# Feedforward_Controller.net
KiCad netlist of a schematic drawn in Altium Designer
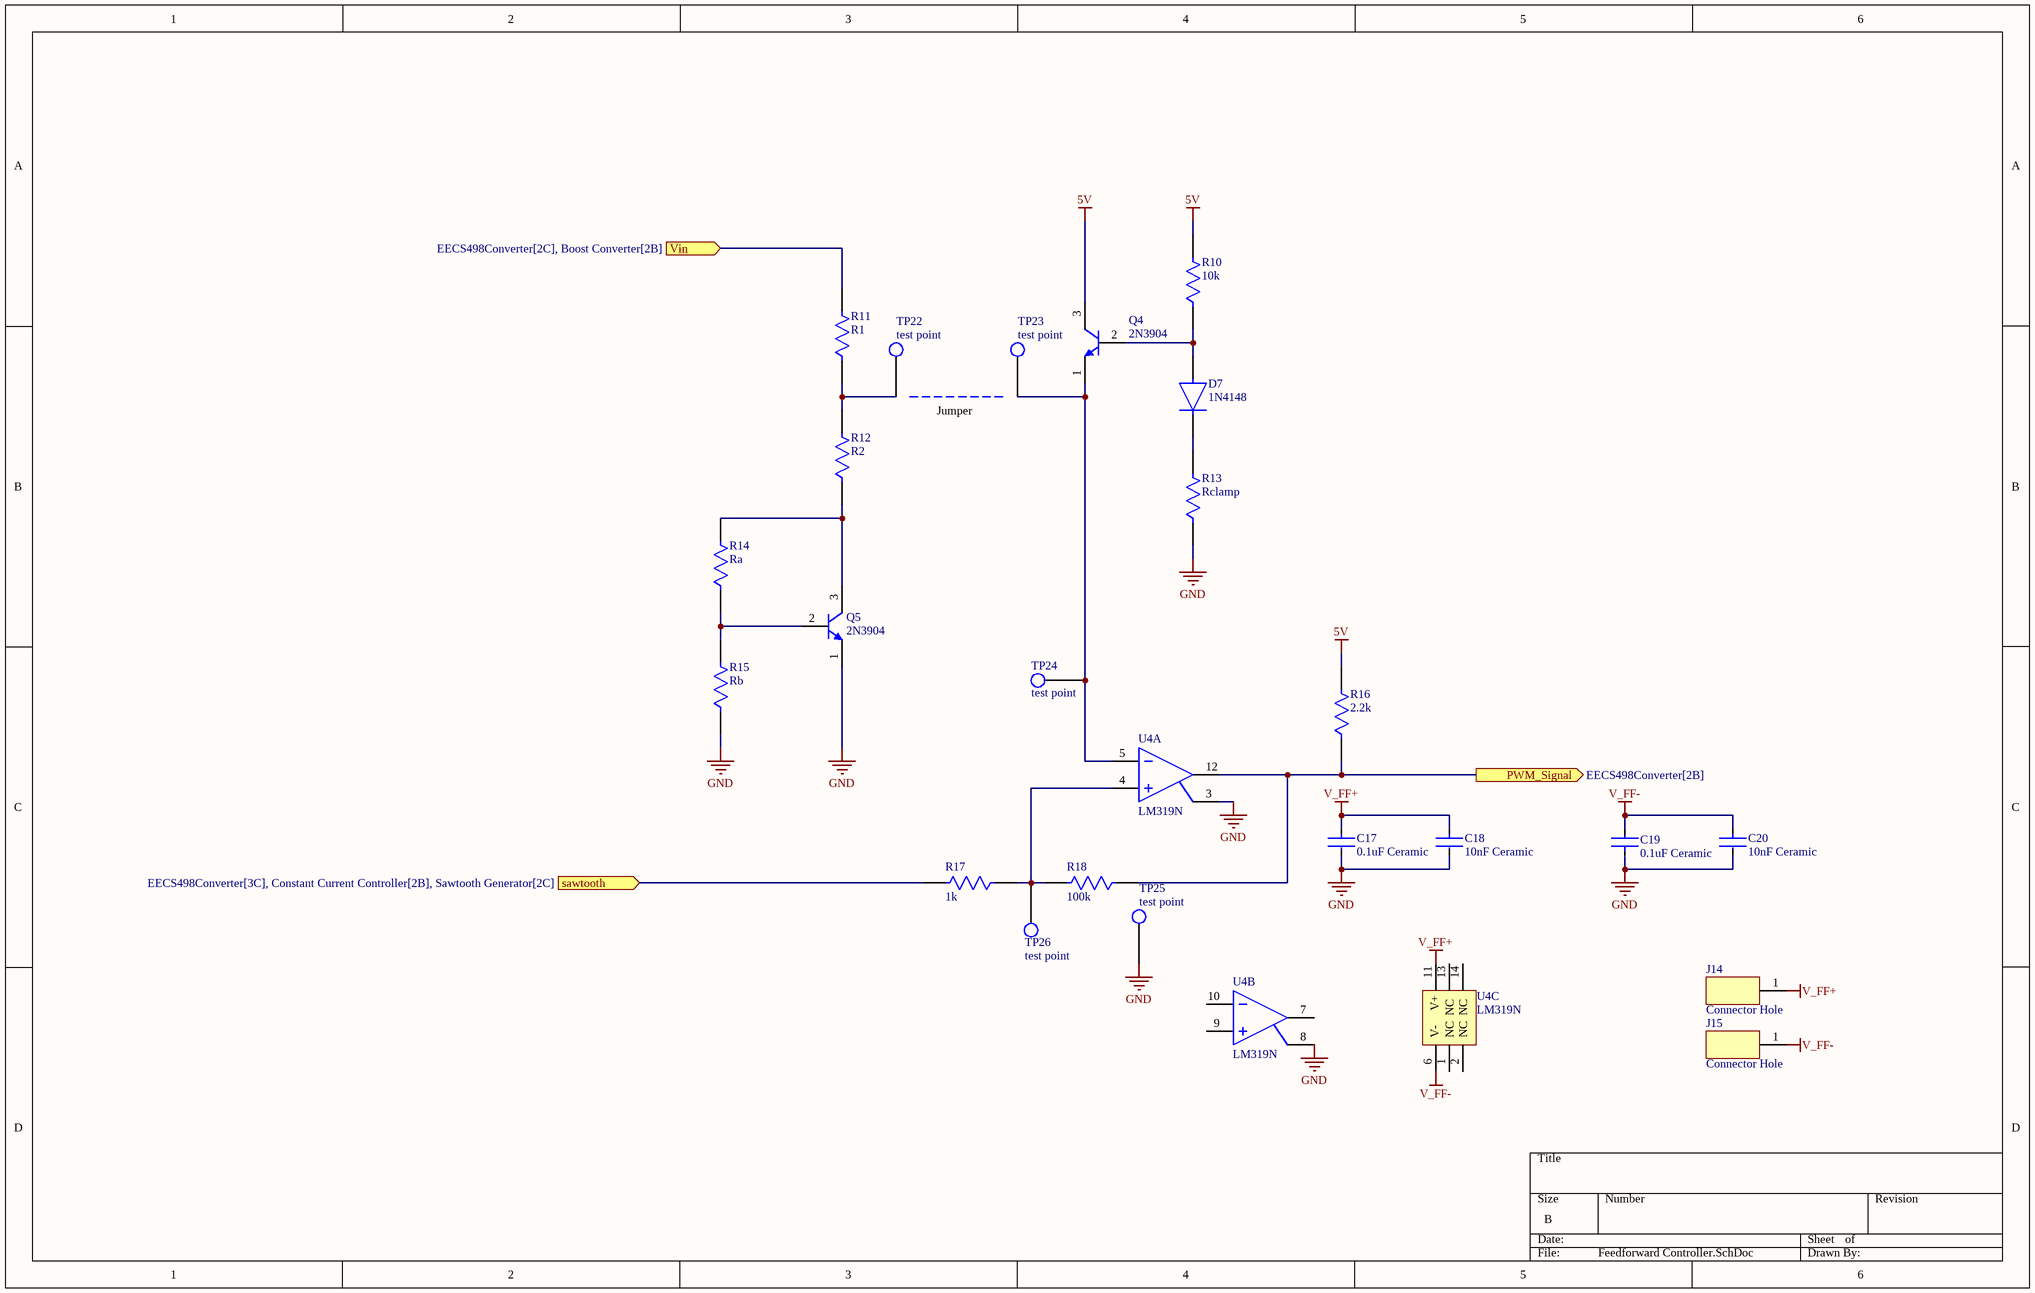
[diagram p0: Feedforward Controller.SchDoc]

(export (version "E")
  (design (tool "Eeschema 10.0.6"))
  (components
    (comp (ref "C17")
      (value "0.1uF Ceramic")
      (footprint "FP-K15H5-MFG")
      (description "CAP CER 0.1UF 50V X7R RADIAL")
      (fields (field (name "TOLERANCE") "10%") (field (name "VOLTAGE") "50V"))
      (libsource (lib "EECS498Converter") (part "0.1uF Capacitor"))
    )
    (comp (ref "C18")
      (value "10nF Ceramic")
      (footprint "FP-K15H5-MFG")
      (description "CAP CER 10nF 50V X7R RADIAL")
      (fields (field (name "TOLERANCE") "10%") (field (name "VOLTAGE") "50V"))
      (libsource (lib "EECS498Converter") (part "10nF Capacitor"))
    )
    (comp (ref "C19")
      (value "0.1uF Ceramic")
      (footprint "FP-K15H5-MFG")
      (description "CAP CER 0.1UF 50V X7R RADIAL")
      (fields (field (name "TOLERANCE") "10%") (field (name "VOLTAGE") "50V"))
      (libsource (lib "EECS498Converter") (part "0.1uF Capacitor"))
    )
    (comp (ref "C20")
      (value "10nF Ceramic")
      (footprint "FP-K15H5-MFG")
      (description "CAP CER 10nF 50V X7R RADIAL")
      (fields (field (name "TOLERANCE") "10%") (field (name "VOLTAGE") "50V"))
      (libsource (lib "EECS498Converter") (part "10nF Capacitor"))
    )
    (comp (ref "D7")
      (value "1N4148")
      (footprint "FP-1N4148-MFG")
      (description "DIODE GEN PURP 100V 200MA DO35")
      (fields (field (name "VOLTAGE") "100V"))
      (libsource (lib "EECS498Converter") (part "1N4148"))
    )
    (comp (ref "J14")
      (value "Connector Hole")
      (footprint "Connector Hole")
      (libsource (lib "EECS498Converter") (part "Connector Hole"))
    )
    (comp (ref "J15")
      (value "Connector Hole")
      (footprint "Connector Hole")
      (libsource (lib "EECS498Converter") (part "Connector Hole"))
    )
    (comp (ref "Q4")
      (value "2N3904")
      (footprint "2N3906TF")
      (description "General Purpose Transistor, NPN Silicon, 200 mA, 60 V, -55 to 150 degC, 3-Pin TO-92, RoHS, Bulk")
      (fields (field (name "MANUFACTURER") "ONSemiconductor"))
      (libsource (lib "EECS498Converter") (part "2N3904"))
    )
    (comp (ref "Q5")
      (value "2N3904")
      (footprint "2N3906TF")
      (description "General Purpose Transistor, NPN Silicon, 200 mA, 60 V, -55 to 150 degC, 3-Pin TO-92, RoHS, Bulk")
      (fields (field (name "MANUFACTURER") "ONSemiconductor"))
      (libsource (lib "EECS498Converter") (part "2N3904"))
    )
    (comp (ref "R10")
      (value "10k")
      (footprint "FP-RLR07-MFG")
      (description "Resistor, ± 1%, 250 mW, Axial Leaded, Metal Film, Military Reliability")
      (fields (field (name "TOLERANCE") "1%"))
      (libsource (lib "EECS498Converter") (part "Resistor"))
    )
    (comp (ref "R11")
      (value "R1")
      (footprint "FP-RLR07-MFG")
      (description "Resistor, ± 1%, 250 mW, Axial Leaded, Metal Film, Military Reliability")
      (fields (field (name "TOLERANCE") "1%"))
      (libsource (lib "EECS498Converter") (part "Resistor"))
    )
    (comp (ref "R12")
      (value "R2")
      (footprint "FP-RLR07-MFG")
      (description "Resistor, ± 1%, 250 mW, Axial Leaded, Metal Film, Military Reliability")
      (fields (field (name "TOLERANCE") "1%"))
      (libsource (lib "EECS498Converter") (part "Resistor"))
    )
    (comp (ref "R13")
      (value "Rclamp")
      (footprint "FP-RLR07-MFG")
      (description "Resistor, ± 1%, 250 mW, Axial Leaded, Metal Film, Military Reliability")
      (fields (field (name "TOLERANCE") "1%"))
      (libsource (lib "EECS498Converter") (part "Resistor"))
    )
    (comp (ref "R14")
      (value "Ra")
      (footprint "FP-RLR07-MFG")
      (description "Resistor, ± 1%, 250 mW, Axial Leaded, Metal Film, Military Reliability")
      (fields (field (name "TOLERANCE") "1%"))
      (libsource (lib "EECS498Converter") (part "Resistor"))
    )
    (comp (ref "R15")
      (value "Rb")
      (footprint "FP-RLR07-MFG")
      (description "Resistor, ± 1%, 250 mW, Axial Leaded, Metal Film, Military Reliability")
      (fields (field (name "TOLERANCE") "1%"))
      (libsource (lib "EECS498Converter") (part "Resistor"))
    )
    (comp (ref "R16")
      (value "2.2k")
      (footprint "FP-RLR07-MFG")
      (description "Resistor, ± 1%, 250 mW, Axial Leaded, Metal Film, Military Reliability")
      (fields (field (name "TOLERANCE") "1%"))
      (libsource (lib "EECS498Converter") (part "Resistor"))
    )
    (comp (ref "R17")
      (value "1k")
      (footprint "FP-RLR07-MFG")
      (description "Resistor, ± 1%, 250 mW, Axial Leaded, Metal Film, Military Reliability")
      (fields (field (name "TOLERANCE") "1%"))
      (libsource (lib "EECS498Converter") (part "Resistor"))
    )
    (comp (ref "R18")
      (value "100k")
      (footprint "FP-RLR07-MFG")
      (description "Resistor, ± 1%, 250 mW, Axial Leaded, Metal Film, Military Reliability")
      (fields (field (name "TOLERANCE") "1%"))
      (libsource (lib "EECS498Converter") (part "Resistor"))
    )
    (comp (ref "TP22")
      (value "test point")
      (footprint "test point")
      (libsource (lib "EECS498Converter") (part "test point"))
    )
    (comp (ref "TP23")
      (value "test point")
      (footprint "test point")
      (libsource (lib "EECS498Converter") (part "test point"))
    )
    (comp (ref "TP24")
      (value "test point")
      (footprint "test point")
      (libsource (lib "EECS498Converter") (part "test point"))
    )
    (comp (ref "TP25")
      (value "test point")
      (footprint "test point")
      (libsource (lib "EECS498Converter") (part "test point"))
    )
    (comp (ref "TP26")
      (value "test point")
      (footprint "test point")
      (libsource (lib "EECS498Converter") (part "test point"))
    )
    (comp (ref "U4")
      (value "LM319N")
      (footprint "LM319_DIP14")
      (description "High Speed Dual Comparator, 14-pin MDIP")
      (fields (field (name "MANUFACTURER") "Texas Instruments"))
      (libsource (lib "EECS498Converter") (part "LM319N"))
    )
  )
  (nets
    (net (code "1") (name "/PWM_Signal") (class "Default")
      (node (ref "R16") (pin "1") (pinfunction "1_1") (pintype "passive"))
      (node (ref "R18") (pin "1") (pinfunction "1_1") (pintype "passive"))
      (node (ref "U4") (pin "12") (pinfunction "OUT1_12") (pintype "passive"))
    )
    (net (code "2") (name "/Vin") (class "Default")
      (node (ref "R11") (pin "2") (pinfunction "2_2") (pintype "passive"))
    )
    (net (code "3") (name "/sawtooth") (class "Default")
      (node (ref "R17") (pin "2") (pinfunction "2_2") (pintype "passive"))
    )
    (net (code "4") (name "5V") (class "Default")
      (node (ref "Q4") (pin "3") (pinfunction "C_3") (pintype "passive"))
      (node (ref "R10") (pin "2") (pinfunction "2_2") (pintype "passive"))
      (node (ref "R16") (pin "2") (pinfunction "2_2") (pintype "passive"))
    )
    (net (code "5") (name "GND") (class "Default")
      (node (ref "C17") (pin "2") (pinfunction "2_2") (pintype "passive"))
      (node (ref "C18") (pin "2") (pinfunction "2_2") (pintype "passive"))
      (node (ref "C19") (pin "1") (pinfunction "1_1") (pintype "passive"))
      (node (ref "C20") (pin "2") (pinfunction "2_2") (pintype "passive"))
      (node (ref "Q5") (pin "1") (pinfunction "E_1") (pintype "passive"))
      (node (ref "R13") (pin "1") (pinfunction "1_1") (pintype "passive"))
      (node (ref "R15") (pin "1") (pinfunction "1_1") (pintype "passive"))
      (node (ref "TP25") (pin "1") (pintype "passive"))
      (node (ref "U4") (pin "3") (pinfunction "GND1_3") (pintype "passive"))
      (node (ref "U4") (pin "8") (pinfunction "GND2_8") (pintype "passive"))
    )
    (net (code "6") (name "Net-(D7-A)") (class "Default")
      (node (ref "D7") (pin "2") (pinfunction "A_2") (pintype "passive"))
      (node (ref "Q4") (pin "2") (pinfunction "B_2") (pintype "passive"))
      (node (ref "R10") (pin "1") (pinfunction "1_1") (pintype "passive"))
    )
    (net (code "7") (name "Net-(D7-C)") (class "Default")
      (node (ref "D7") (pin "1") (pinfunction "C_1") (pintype "passive"))
      (node (ref "R13") (pin "2") (pinfunction "2_2") (pintype "passive"))
    )
    (net (code "8") (name "Net-(Q4-E)") (class "Default")
      (node (ref "Q4") (pin "1") (pinfunction "E_1") (pintype "passive"))
      (node (ref "TP23") (pin "1") (pintype "passive"))
      (node (ref "TP24") (pin "1") (pintype "passive"))
      (node (ref "U4") (pin "5") (pinfunction "IN1-_5") (pintype "passive"))
    )
    (net (code "9") (name "Net-(Q5-B)") (class "Default")
      (node (ref "Q5") (pin "2") (pinfunction "B_2") (pintype "passive"))
      (node (ref "R14") (pin "1") (pinfunction "1_1") (pintype "passive"))
      (node (ref "R15") (pin "2") (pinfunction "2_2") (pintype "passive"))
    )
    (net (code "10") (name "Net-(Q5-C)") (class "Default")
      (node (ref "Q5") (pin "3") (pinfunction "C_3") (pintype "passive"))
      (node (ref "R12") (pin "1") (pinfunction "1_1") (pintype "passive"))
      (node (ref "R14") (pin "2") (pinfunction "2_2") (pintype "passive"))
    )
    (net (code "11") (name "Net-(R11-Pad1)") (class "Default")
      (node (ref "R11") (pin "1") (pinfunction "1_1") (pintype "passive"))
      (node (ref "R12") (pin "2") (pinfunction "2_2") (pintype "passive"))
      (node (ref "TP22") (pin "1") (pintype "passive"))
    )
    (net (code "12") (name "Net-(U4A-IN1+)") (class "Default")
      (node (ref "R17") (pin "1") (pinfunction "1_1") (pintype "passive"))
      (node (ref "R18") (pin "2") (pinfunction "2_2") (pintype "passive"))
      (node (ref "TP26") (pin "1") (pintype "passive"))
      (node (ref "U4") (pin "4") (pinfunction "IN1+_4") (pintype "passive"))
    )
    (net (code "13") (name "V_FF+") (class "Default")
      (node (ref "C17") (pin "1") (pinfunction "1_1") (pintype "passive"))
      (node (ref "C18") (pin "1") (pinfunction "1_1") (pintype "passive"))
      (node (ref "J14") (pin "1") (pinfunction "1_1") (pintype "passive"))
      (node (ref "U4") (pin "11") (pinfunction "V+_11") (pintype "passive"))
    )
    (net (code "14") (name "V_FF-") (class "Default")
      (node (ref "C19") (pin "2") (pinfunction "2_2") (pintype "passive"))
      (node (ref "C20") (pin "1") (pinfunction "1_1") (pintype "passive"))
      (node (ref "J15") (pin "1") (pinfunction "1_1") (pintype "passive"))
      (node (ref "U4") (pin "6") (pinfunction "V-_6") (pintype "passive"))
    )
    (net (code "15") (name "unconnected-(U4B-IN2+-Pad9)") (class "Default")
      (node (ref "U4") (pin "9") (pinfunction "IN2+_9") (pintype "passive"))
    )
    (net (code "16") (name "unconnected-(U4B-IN2--Pad10)") (class "Default")
      (node (ref "U4") (pin "10") (pinfunction "IN2-_10") (pintype "passive"))
    )
    (net (code "17") (name "unconnected-(U4B-OUT2-Pad7)") (class "Default")
      (node (ref "U4") (pin "7") (pinfunction "OUT2_7") (pintype "passive"))
    )
    (net (code "18") (name "unconnected-(U4C-NC-Pad1)") (class "Default")
      (node (ref "U4") (pin "1") (pinfunction "NC_1") (pintype "passive"))
    )
    (net (code "19") (name "unconnected-(U4C-NC-Pad2)") (class "Default")
      (node (ref "U4") (pin "2") (pinfunction "NC_2") (pintype "passive"))
    )
    (net (code "20") (name "unconnected-(U4C-NC-Pad13)") (class "Default")
      (node (ref "U4") (pin "13") (pinfunction "NC_13") (pintype "passive"))
    )
    (net (code "21") (name "unconnected-(U4C-NC-Pad14)") (class "Default")
      (node (ref "U4") (pin "14") (pinfunction "NC_14") (pintype "passive"))
    )
  )
)
